# Audio_IO_Switch_-_SCH.net
KiCad netlist of a schematic drawn in Altium Designer
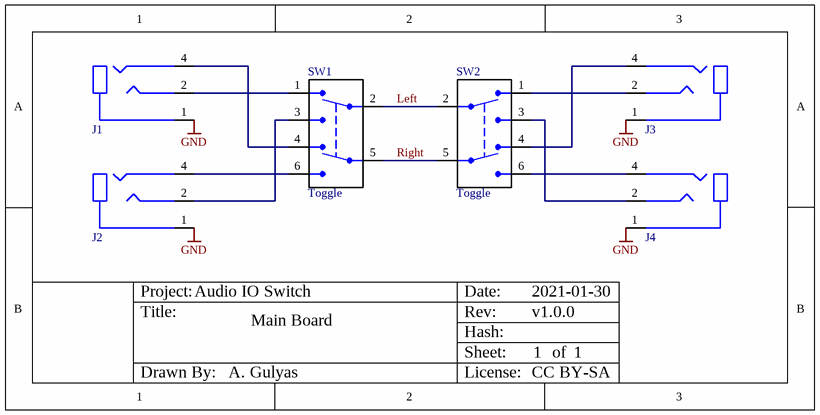
[diagram p0: Audio IO Switch - SCH.SchDoc]

(export (version "E")
  (design (tool "Eeschema 10.0.6"))
  (components
    (comp (ref "J1")
      (value "Jack - TRS - 35RAPC2BV4")
      (footprint "Jack - TRS - MJ-3502")
      (description "CONN JACK STEREO 3.5MM R/A")
      (fields (field (name "MFG") "Switchcraft"))
      (libsource (lib "Audio IO Switch - SchLib") (part "Jack - TRS - 35RAPC2BV4"))
    )
    (comp (ref "J2")
      (value "Jack - TRS - 35RAPC2BV4")
      (footprint "Jack - TRS - MJ-3502")
      (description "CONN JACK STEREO 3.5MM R/A")
      (fields (field (name "MFG") "Switchcraft"))
      (libsource (lib "Audio IO Switch - SchLib") (part "Jack - TRS - 35RAPC2BV4"))
    )
    (comp (ref "J3")
      (value "Jack - TRS - 35RAPC2BV4")
      (footprint "Jack - TRS - MJ-3502")
      (description "CONN JACK STEREO 3.5MM R/A")
      (fields (field (name "MFG") "Switchcraft"))
      (libsource (lib "Audio IO Switch - SchLib") (part "Jack - TRS - 35RAPC2BV4"))
    )
    (comp (ref "J4")
      (value "Jack - TRS - 35RAPC2BV4")
      (footprint "Jack - TRS - MJ-3502")
      (description "CONN JACK STEREO 3.5MM R/A")
      (fields (field (name "MFG") "Switchcraft"))
      (libsource (lib "Audio IO Switch - SchLib") (part "Jack - TRS - 35RAPC2BV4"))
    )
    (comp (ref "SW1")
      (value "Toggle")
      (footprint "SW - toggle - RA - 100DP1T1B1M6QE")
      (description "SWITCH TOGGLE DPDT 5A 120V")
      (fields (field (name "MFG") "E-Switch"))
      (libsource (lib "") (part "SW - DPDT - 100DP1T1B1M6QE_1"))
    )
    (comp (ref "SW2")
      (value "Toggle")
      (footprint "SW - toggle - RA - 100DP1T1B1M6QE")
      (description "SWITCH TOGGLE DPDT 5A 120V")
      (fields (field (name "MFG") "E-Switch"))
      (libsource (lib "Audio IO Switch - SchLib") (part "SW - DPDT - 100DP1T1B1M6QE"))
    )
  )
  (nets
    (net (code "1") (name "/Left") (class "Default")
      (node (ref "SW1") (pin "2") (pinfunction "2_2") (pintype "passive"))
      (node (ref "SW2") (pin "2") (pinfunction "2_2") (pintype "passive"))
    )
    (net (code "2") (name "/Right") (class "Default")
      (node (ref "SW1") (pin "5") (pinfunction "5_5") (pintype "passive"))
      (node (ref "SW2") (pin "5") (pinfunction "5_5") (pintype "passive"))
    )
    (net (code "3") (name "GND") (class "Default")
      (node (ref "J1") (pin "1") (pinfunction "1_1") (pintype "passive"))
      (node (ref "J2") (pin "1") (pinfunction "1_1") (pintype "passive"))
      (node (ref "J3") (pin "1") (pinfunction "1_1") (pintype "passive"))
      (node (ref "J4") (pin "1") (pinfunction "1_1") (pintype "passive"))
    )
    (net (code "4") (name "Net-(J1-Pad2)") (class "Default")
      (node (ref "J1") (pin "2") (pinfunction "2_2") (pintype "passive"))
      (node (ref "SW1") (pin "1") (pinfunction "1_1") (pintype "passive"))
    )
    (net (code "5") (name "Net-(J1-Pad4)") (class "Default")
      (node (ref "J1") (pin "4") (pinfunction "4_4") (pintype "passive"))
      (node (ref "SW1") (pin "4") (pinfunction "4_4") (pintype "passive"))
    )
    (net (code "6") (name "Net-(J2-Pad2)") (class "Default")
      (node (ref "J2") (pin "2") (pinfunction "2_2") (pintype "passive"))
      (node (ref "SW1") (pin "3") (pinfunction "3_3") (pintype "passive"))
    )
    (net (code "7") (name "Net-(J2-Pad4)") (class "Default")
      (node (ref "J2") (pin "4") (pinfunction "4_4") (pintype "passive"))
      (node (ref "SW1") (pin "6") (pinfunction "6_6") (pintype "passive"))
    )
    (net (code "8") (name "Net-(J3-Pad2)") (class "Default")
      (node (ref "J3") (pin "2") (pinfunction "2_2") (pintype "passive"))
      (node (ref "SW2") (pin "1") (pinfunction "1_1") (pintype "passive"))
    )
    (net (code "9") (name "Net-(J3-Pad4)") (class "Default")
      (node (ref "J3") (pin "4") (pinfunction "4_4") (pintype "passive"))
      (node (ref "SW2") (pin "4") (pinfunction "4_4") (pintype "passive"))
    )
    (net (code "10") (name "Net-(J4-Pad2)") (class "Default")
      (node (ref "J4") (pin "2") (pinfunction "2_2") (pintype "passive"))
      (node (ref "SW2") (pin "3") (pinfunction "3_3") (pintype "passive"))
    )
    (net (code "11") (name "Net-(J4-Pad4)") (class "Default")
      (node (ref "J4") (pin "4") (pinfunction "4_4") (pintype "passive"))
      (node (ref "SW2") (pin "6") (pinfunction "6_6") (pintype "passive"))
    )
  )
)
